# CapacitorBank.net
KiCad netlist of a schematic drawn in Altium Designer
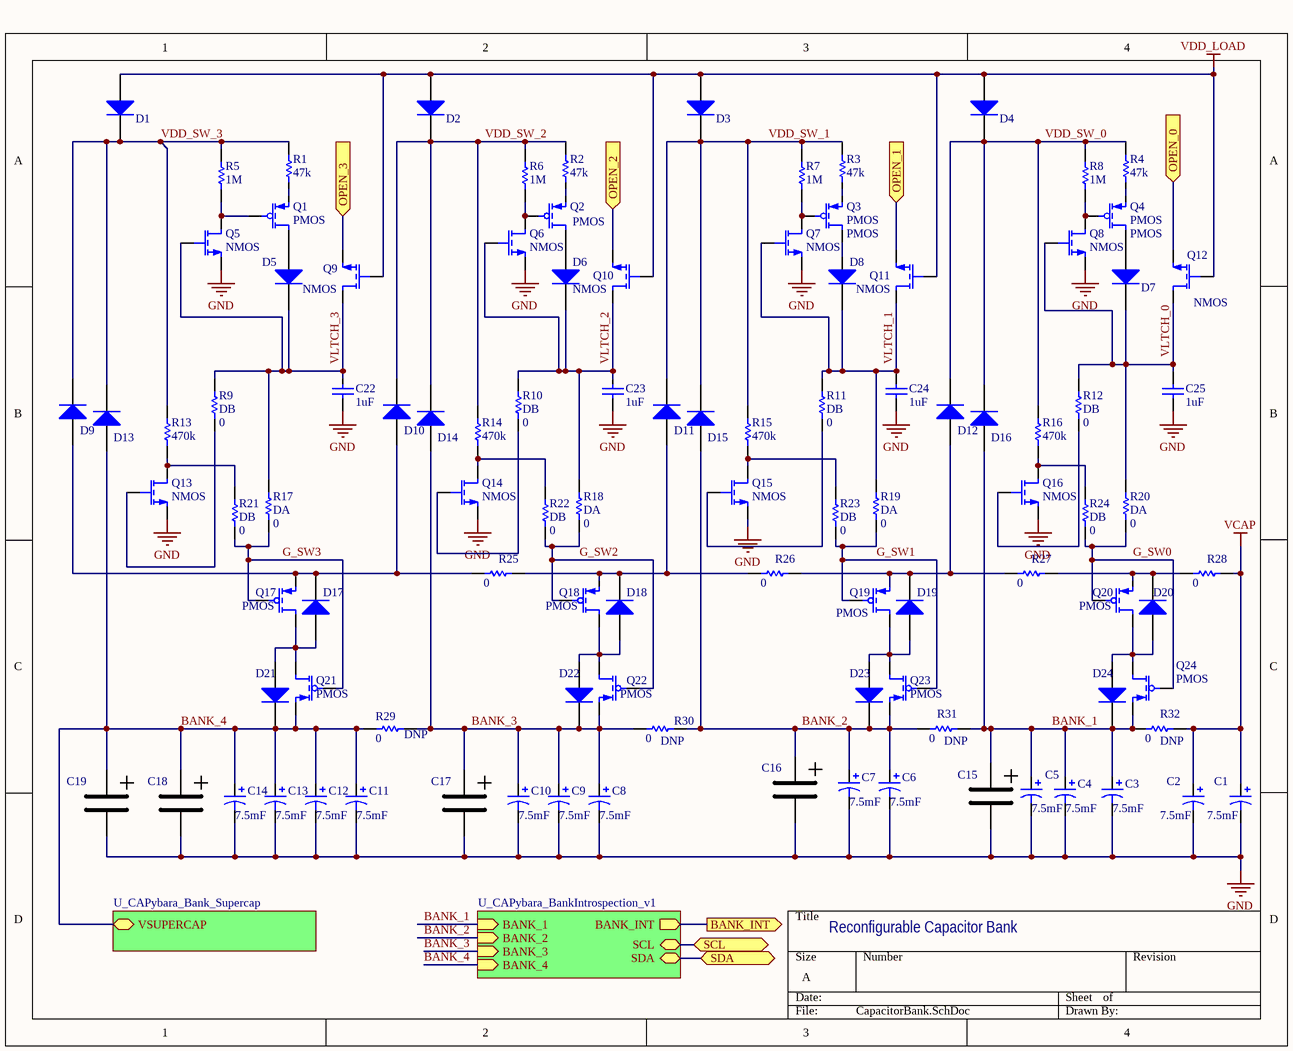
[diagram p0: CapacitorBank.SchDoc]

(export (version "E")
  (design (tool "Eeschema 10.0.6"))
  (components
    (comp (ref "C1")
      (value "7.5mF")
      (footprint "CAP_CPH3225A")
      (description "Polarized Capacitor")
      (fields
        (field (name "DIGI-KEY PART NUMBER") "728-1083-1-ND")
        (field (name "MANUFACTURER PART NUMBER") "CPX3225A752D")
      )
      (libsource (lib "DRP_Basic_2014") (part "Cap - Polarized"))
    )
    (comp (ref "C2")
      (value "7.5mF")
      (footprint "CAP_CPH3225A")
      (description "Polarized Capacitor")
      (fields
        (field (name "DIGI-KEY PART NUMBER") "728-1083-1-ND")
        (field (name "MANUFACTURER PART NUMBER") "CPX3225A752D")
      )
      (libsource (lib "DRP_Basic_2014") (part "Cap - Polarized"))
    )
    (comp (ref "C3")
      (value "7.5mF")
      (footprint "CAP_CPH3225A")
      (description "Polarized Capacitor")
      (fields
        (field (name "DIGI-KEY PART NUMBER") "728-1083-1-ND")
        (field (name "MANUFACTURER PART NUMBER") "CPX3225A752D")
      )
      (libsource (lib "DRP_Basic_2014") (part "Cap - Polarized"))
    )
    (comp (ref "C4")
      (value "7.5mF")
      (footprint "CAP_CPH3225A")
      (description "Polarized Capacitor")
      (fields
        (field (name "DIGI-KEY PART NUMBER") "728-1083-1-ND")
        (field (name "MANUFACTURER PART NUMBER") "CPX3225A752D")
      )
      (libsource (lib "DRP_Basic_2014") (part "Cap - Polarized"))
    )
    (comp (ref "C5")
      (value "7.5mF")
      (footprint "CAP_CPH3225A")
      (description "Polarized Capacitor")
      (fields
        (field (name "DIGI-KEY PART NUMBER") "728-1083-1-ND")
        (field (name "MANUFACTURER PART NUMBER") "CPX3225A752D")
      )
      (libsource (lib "DRP_Basic_2014") (part "Cap - Polarized"))
    )
    (comp (ref "C6")
      (value "7.5mF")
      (footprint "CAP_CPH3225A")
      (description "Polarized Capacitor")
      (fields
        (field (name "DIGI-KEY PART NUMBER") "728-1083-1-ND")
        (field (name "MANUFACTURER PART NUMBER") "CPX3225A752D")
      )
      (libsource (lib "DRP_Basic_2014") (part "Cap - Polarized"))
    )
    (comp (ref "C7")
      (value "7.5mF")
      (footprint "CAP_CPH3225A")
      (description "Polarized Capacitor")
      (fields
        (field (name "DIGI-KEY PART NUMBER") "728-1083-1-ND")
        (field (name "MANUFACTURER PART NUMBER") "CPX3225A752D")
      )
      (libsource (lib "DRP_Basic_2014") (part "Cap - Polarized"))
    )
    (comp (ref "C8")
      (value "7.5mF")
      (footprint "CAP_CPH3225A")
      (description "Polarized Capacitor")
      (fields
        (field (name "DIGI-KEY PART NUMBER") "728-1083-1-ND")
        (field (name "MANUFACTURER PART NUMBER") "CPX3225A752D")
      )
      (libsource (lib "DRP_Basic_2014") (part "Cap - Polarized"))
    )
    (comp (ref "C9")
      (value "7.5mF")
      (footprint "CAP_CPH3225A")
      (description "Polarized Capacitor")
      (fields
        (field (name "DIGI-KEY PART NUMBER") "728-1083-1-ND")
        (field (name "MANUFACTURER PART NUMBER") "CPX3225A752D")
      )
      (libsource (lib "DRP_Basic_2014") (part "Cap - Polarized"))
    )
    (comp (ref "C10")
      (value "7.5mF")
      (footprint "CAP_CPH3225A")
      (description "Polarized Capacitor")
      (fields
        (field (name "DIGI-KEY PART NUMBER") "728-1083-1-ND")
        (field (name "MANUFACTURER PART NUMBER") "CPX3225A752D")
      )
      (libsource (lib "DRP_Basic_2014") (part "Cap - Polarized"))
    )
    (comp (ref "C11")
      (value "7.5mF")
      (footprint "CAP_CPH3225A")
      (description "Polarized Capacitor")
      (fields
        (field (name "DIGI-KEY PART NUMBER") "728-1083-1-ND")
        (field (name "MANUFACTURER PART NUMBER") "CPX3225A752D")
      )
      (libsource (lib "DRP_Basic_2014") (part "Cap - Polarized"))
    )
    (comp (ref "C12")
      (value "7.5mF")
      (footprint "CAP_CPH3225A")
      (description "Polarized Capacitor")
      (fields
        (field (name "DIGI-KEY PART NUMBER") "728-1083-1-ND")
        (field (name "MANUFACTURER PART NUMBER") "CPX3225A752D")
      )
      (libsource (lib "DRP_Basic_2014") (part "Cap - Polarized"))
    )
    (comp (ref "C13")
      (value "7.5mF")
      (footprint "CAP_CPH3225A")
      (description "Polarized Capacitor")
      (fields
        (field (name "DIGI-KEY PART NUMBER") "728-1083-1-ND")
        (field (name "MANUFACTURER PART NUMBER") "CPX3225A752D")
      )
      (libsource (lib "DRP_Basic_2014") (part "Cap - Polarized"))
    )
    (comp (ref "C14")
      (value "7.5mF")
      (footprint "CAP_CPH3225A")
      (description "Polarized Capacitor")
      (fields
        (field (name "DIGI-KEY PART NUMBER") "728-1083-1-ND")
        (field (name "MANUFACTURER PART NUMBER") "CPX3225A752D")
      )
      (libsource (lib "DRP_Basic_2014") (part "Cap - Polarized"))
    )
    (comp (ref "C15")
      (value "304DCN2R7SCBB")
      (footprint "CAP_ILLINOIS_DCN")
      (description "EDLC Supercap")
      (fields
        (field (name "DISTRIBUTOR PART NUMBER") "598-304DCN2R7SCBB")
        (field (name "MANUFACTURER") "Illinois Capacitor / CDE")
      )
      (libsource (lib "Sprite") (part "SUPERCAP"))
    )
    (comp (ref "C16")
      (value "304DCN2R7SCBB")
      (footprint "CAP_ILLINOIS_DCN")
      (description "EDLC Supercap")
      (fields
        (field (name "DISTRIBUTOR PART NUMBER") "598-304DCN2R7SCBB")
        (field (name "MANUFACTURER") "Illinois Capacitor / CDE")
      )
      (libsource (lib "Sprite") (part "SUPERCAP"))
    )
    (comp (ref "C17")
      (value "304DCN2R7SCBB")
      (footprint "CAP_ILLINOIS_DCN")
      (description "EDLC Supercap")
      (fields
        (field (name "DISTRIBUTOR PART NUMBER") "598-304DCN2R7SCBB")
        (field (name "MANUFACTURER") "Illinois Capacitor / CDE")
      )
      (libsource (lib "Sprite") (part "SUPERCAP"))
    )
    (comp (ref "C18")
      (value "304DCN2R7SCBB")
      (footprint "CAP_ILLINOIS_DCN")
      (description "EDLC Supercap")
      (fields
        (field (name "DISTRIBUTOR PART NUMBER") "598-304DCN2R7SCBB")
        (field (name "MANUFACTURER") "Illinois Capacitor / CDE")
      )
      (libsource (lib "Sprite") (part "SUPERCAP"))
    )
    (comp (ref "C19")
      (value "304DCN2R7SCBB")
      (footprint "CAP_ILLINOIS_DCN")
      (description "EDLC Supercap")
      (fields
        (field (name "DISTRIBUTOR PART NUMBER") "598-304DCN2R7SCBB")
        (field (name "MANUFACTURER") "Illinois Capacitor / CDE")
      )
      (libsource (lib "Sprite") (part "SUPERCAP"))
    )
    (comp (ref "C22")
      (value "1uF")
      (footprint "0603")
      (description "Ceramic Capacitor (Surface Mount)")
      (fields
        (field (name "MANUFACTURER") "Murata Electronics North America")
        (field (name "MANUFACTURER PART NUMBER") "GRM188R61A105KA61D")
      )
      (libsource (lib "DRP_Basic_2014") (part "Cap"))
    )
    (comp (ref "C23")
      (value "1uF")
      (footprint "0603")
      (description "Ceramic Capacitor (Surface Mount)")
      (fields
        (field (name "MANUFACTURER") "Murata Electronics North America")
        (field (name "MANUFACTURER PART NUMBER") "GRM188R61A105KA61D")
      )
      (libsource (lib "DRP_Basic_2014") (part "Cap"))
    )
    (comp (ref "C24")
      (value "1uF")
      (footprint "0603")
      (description "Ceramic Capacitor (Surface Mount)")
      (fields
        (field (name "MANUFACTURER") "Murata Electronics North America")
        (field (name "MANUFACTURER PART NUMBER") "GRM188R61A105KA61D")
      )
      (libsource (lib "DRP_Basic_2014") (part "Cap"))
    )
    (comp (ref "C25")
      (value "1uF")
      (footprint "0603")
      (description "Ceramic Capacitor (Surface Mount)")
      (fields
        (field (name "MANUFACTURER") "Murata Electronics North America")
        (field (name "MANUFACTURER PART NUMBER") "GRM188R61A105KA61D")
      )
      (libsource (lib "DRP_Basic_2014") (part "Cap"))
    )
    (comp (ref "D1")
      (value "Diode")
      (footprint "SOD-523")
      (description "General Purpose Diode")
      (fields
        (field (name "MANUFACTURER") "Vishay Semiconductor")
        (field (name "MANUFACTURER PART NUMBER") "BAS40-02V-V-G-08")
      )
      (libsource (lib "DRP_Basic_2014") (part "Diode"))
    )
    (comp (ref "D2")
      (value "Diode")
      (footprint "SOD-523")
      (description "General Purpose Diode")
      (fields
        (field (name "MANUFACTURER") "Vishay Semiconductor")
        (field (name "MANUFACTURER PART NUMBER") "BAS40-02V-V-G-08")
      )
      (libsource (lib "DRP_Basic_2014") (part "Diode"))
    )
    (comp (ref "D3")
      (value "Diode")
      (footprint "SOD-523")
      (description "General Purpose Diode")
      (fields
        (field (name "MANUFACTURER") "Vishay Semiconductor")
        (field (name "MANUFACTURER PART NUMBER") "BAS40-02V-V-G-08")
      )
      (libsource (lib "DRP_Basic_2014") (part "Diode"))
    )
    (comp (ref "D4")
      (value "Diode")
      (footprint "SOD-523")
      (description "General Purpose Diode")
      (fields
        (field (name "MANUFACTURER") "Vishay Semiconductor")
        (field (name "MANUFACTURER PART NUMBER") "BAS40-02V-V-G-08")
      )
      (libsource (lib "DRP_Basic_2014") (part "Diode"))
    )
    (comp (ref "D5")
      (value "Diode")
      (footprint "SOD-523")
      (description "General Purpose Diode")
      (fields
        (field (name "MANUFACTURER") "Vishay Semiconductor")
        (field (name "MANUFACTURER PART NUMBER") "BAS40-02V-V-G-08")
      )
      (libsource (lib "DRP_Basic_2014") (part "Diode"))
    )
    (comp (ref "D6")
      (value "Diode")
      (footprint "SOD-523")
      (description "General Purpose Diode")
      (fields
        (field (name "MANUFACTURER") "Vishay Semiconductor")
        (field (name "MANUFACTURER PART NUMBER") "BAS40-02V-V-G-08")
      )
      (libsource (lib "DRP_Basic_2014") (part "Diode"))
    )
    (comp (ref "D7")
      (value "Diode")
      (footprint "SOD-523")
      (description "General Purpose Diode")
      (fields
        (field (name "MANUFACTURER") "Vishay Semiconductor")
        (field (name "MANUFACTURER PART NUMBER") "BAS40-02V-V-G-08")
      )
      (libsource (lib "DRP_Basic_2014") (part "Diode"))
    )
    (comp (ref "D8")
      (value "Diode")
      (footprint "SOD-523")
      (description "General Purpose Diode")
      (fields
        (field (name "MANUFACTURER") "Vishay Semiconductor")
        (field (name "MANUFACTURER PART NUMBER") "BAS40-02V-V-G-08")
      )
      (libsource (lib "") (part "Diode_1"))
    )
    (comp (ref "D9")
      (value "Diode")
      (footprint "SOD-523")
      (description "General Purpose Diode")
      (fields
        (field (name "MANUFACTURER") "Vishay Semiconductor")
        (field (name "MANUFACTURER PART NUMBER") "BAS40-02V-V-G-08")
      )
      (libsource (lib "DRP_Basic_2014") (part "Diode"))
    )
    (comp (ref "D10")
      (value "Diode")
      (footprint "SOD-523")
      (description "General Purpose Diode")
      (fields
        (field (name "MANUFACTURER") "Vishay Semiconductor")
        (field (name "MANUFACTURER PART NUMBER") "BAS40-02V-V-G-08")
      )
      (libsource (lib "DRP_Basic_2014") (part "Diode"))
    )
    (comp (ref "D11")
      (value "Diode")
      (footprint "SOD-523")
      (description "General Purpose Diode")
      (fields
        (field (name "MANUFACTURER") "Vishay Semiconductor")
        (field (name "MANUFACTURER PART NUMBER") "BAS40-02V-V-G-08")
      )
      (libsource (lib "DRP_Basic_2014") (part "Diode"))
    )
    (comp (ref "D12")
      (value "Diode")
      (footprint "SOD-523")
      (description "General Purpose Diode")
      (fields
        (field (name "MANUFACTURER") "Vishay Semiconductor")
        (field (name "MANUFACTURER PART NUMBER") "BAS40-02V-V-G-08")
      )
      (libsource (lib "DRP_Basic_2014") (part "Diode"))
    )
    (comp (ref "D13")
      (value "Diode")
      (footprint "SOD-523")
      (description "General Purpose Diode")
      (fields
        (field (name "MANUFACTURER") "Vishay Semiconductor")
        (field (name "MANUFACTURER PART NUMBER") "BAS40-02V-V-G-08")
      )
      (libsource (lib "DRP_Basic_2014") (part "Diode"))
    )
    (comp (ref "D14")
      (value "Diode")
      (footprint "SOD-523")
      (description "General Purpose Diode")
      (fields
        (field (name "MANUFACTURER") "Vishay Semiconductor")
        (field (name "MANUFACTURER PART NUMBER") "BAS40-02V-V-G-08")
      )
      (libsource (lib "DRP_Basic_2014") (part "Diode"))
    )
    (comp (ref "D15")
      (value "Diode")
      (footprint "SOD-523")
      (description "General Purpose Diode")
      (fields
        (field (name "MANUFACTURER") "Vishay Semiconductor")
        (field (name "MANUFACTURER PART NUMBER") "BAS40-02V-V-G-08")
      )
      (libsource (lib "DRP_Basic_2014") (part "Diode"))
    )
    (comp (ref "D16")
      (value "Diode")
      (footprint "SOD-523")
      (description "General Purpose Diode")
      (fields
        (field (name "MANUFACTURER") "Vishay Semiconductor")
        (field (name "MANUFACTURER PART NUMBER") "BAS40-02V-V-G-08")
      )
      (libsource (lib "DRP_Basic_2014") (part "Diode"))
    )
    (comp (ref "D17")
      (value "Diode")
      (footprint "SOD-523")
      (description "General Purpose Diode")
      (fields
        (field (name "MANUFACTURER") "Vishay Semiconductor")
        (field (name "MANUFACTURER PART NUMBER") "BAS40-02V-V-G-08")
      )
      (libsource (lib "DRP_Basic_2014") (part "Diode"))
    )
    (comp (ref "D18")
      (value "Diode")
      (footprint "SOD-523")
      (description "General Purpose Diode")
      (fields
        (field (name "MANUFACTURER") "Vishay Semiconductor")
        (field (name "MANUFACTURER PART NUMBER") "BAS40-02V-V-G-08")
      )
      (libsource (lib "DRP_Basic_2014") (part "Diode"))
    )
    (comp (ref "D19")
      (value "Diode")
      (footprint "SOD-523")
      (description "General Purpose Diode")
      (fields
        (field (name "MANUFACTURER") "Vishay Semiconductor")
        (field (name "MANUFACTURER PART NUMBER") "BAS40-02V-V-G-08")
      )
      (libsource (lib "DRP_Basic_2014") (part "Diode"))
    )
    (comp (ref "D20")
      (value "Diode")
      (footprint "SOD-523")
      (description "General Purpose Diode")
      (fields
        (field (name "MANUFACTURER") "Vishay Semiconductor")
        (field (name "MANUFACTURER PART NUMBER") "BAS40-02V-V-G-08")
      )
      (libsource (lib "DRP_Basic_2014") (part "Diode"))
    )
    (comp (ref "D21")
      (value "Diode")
      (footprint "SOD-523")
      (description "General Purpose Diode")
      (fields
        (field (name "MANUFACTURER") "Vishay Semiconductor")
        (field (name "MANUFACTURER PART NUMBER") "BAS40-02V-V-G-08")
      )
      (libsource (lib "DRP_Basic_2014") (part "Diode"))
    )
    (comp (ref "D22")
      (value "Diode")
      (footprint "SOD-523")
      (description "General Purpose Diode")
      (fields
        (field (name "MANUFACTURER") "Vishay Semiconductor")
        (field (name "MANUFACTURER PART NUMBER") "BAS40-02V-V-G-08")
      )
      (libsource (lib "DRP_Basic_2014") (part "Diode"))
    )
    (comp (ref "D23")
      (value "Diode")
      (footprint "SOD-523")
      (description "General Purpose Diode")
      (fields
        (field (name "MANUFACTURER") "Vishay Semiconductor")
        (field (name "MANUFACTURER PART NUMBER") "BAS40-02V-V-G-08")
      )
      (libsource (lib "DRP_Basic_2014") (part "Diode"))
    )
    (comp (ref "D24")
      (value "Diode")
      (footprint "SOD-523")
      (description "General Purpose Diode")
      (fields
        (field (name "MANUFACTURER") "Vishay Semiconductor")
        (field (name "MANUFACTURER PART NUMBER") "BAS40-02V-V-G-08")
      )
      (libsource (lib "DRP_Basic_2014") (part "Diode"))
    )
    (comp (ref "Q1")
      (value "PMOS")
      (footprint "SOT23 - N")
      (description "P-Channel MOSFET")
      (fields
        (field (name "DIGI-KEY PART NUMBER") "1727-2531-1-ND")
        (field (name "MANUFACTURER PART NUMBER") "PMV30XPEAR")
      )
      (libsource (lib "DRP_Basic_2014") (part "MOSFET-P"))
    )
    (comp (ref "Q2")
      (value "PMOS")
      (footprint "SOT23 - N")
      (description "P-Channel MOSFET")
      (fields
        (field (name "DIGI-KEY PART NUMBER") "1727-2531-1-ND")
        (field (name "MANUFACTURER PART NUMBER") "PMV30XPEAR")
      )
      (libsource (lib "DRP_Basic_2014") (part "MOSFET-P"))
    )
    (comp (ref "Q3")
      (value "PMOS")
      (footprint "SOT23 - N")
      (description "P-Channel MOSFET")
      (fields
        (field (name "DIGI-KEY PART NUMBER") "1727-2531-1-ND")
        (field (name "MANUFACTURER PART NUMBER") "PMV30XPEAR")
        (field (name "ALTIUM_VALUE") "PMOS")
      )
      (libsource (lib "DRP_Basic_2014") (part "MOSFET-P"))
    )
    (comp (ref "Q4")
      (value "PMOS")
      (footprint "SOT23 - N")
      (description "P-Channel MOSFET")
      (fields
        (field (name "DIGI-KEY PART NUMBER") "1727-2531-1-ND")
        (field (name "MANUFACTURER PART NUMBER") "PMV30XPEAR")
        (field (name "ALTIUM_VALUE") "PMOS")
      )
      (libsource (lib "DRP_Basic_2014") (part "MOSFET-P"))
    )
    (comp (ref "Q5")
      (value "NMOS")
      (footprint "SOT23 - N")
      (description "N-Channel MOSFET")
      (fields
        (field (name "DIGI-KEY PART NUMBER") "SI2302CDS-T1-E3CT-ND")
        (field (name "MANUFACTURER PART NUMBER") "SI2302CDS-T1-E3")
      )
      (libsource (lib "DRP_Basic_2014") (part "MOSFET-N"))
    )
    (comp (ref "Q6")
      (value "NMOS")
      (footprint "SOT23 - N")
      (description "N-Channel MOSFET")
      (fields
        (field (name "DIGI-KEY PART NUMBER") "SI2302CDS-T1-E3CT-ND")
        (field (name "MANUFACTURER PART NUMBER") "SI2302CDS-T1-E3")
      )
      (libsource (lib "DRP_Basic_2014") (part "MOSFET-N"))
    )
    (comp (ref "Q7")
      (value "NMOS")
      (footprint "SOT23 - N")
      (description "N-Channel MOSFET")
      (fields
        (field (name "DIGI-KEY PART NUMBER") "SI2302CDS-T1-E3CT-ND")
        (field (name "MANUFACTURER PART NUMBER") "SI2302CDS-T1-E3")
      )
      (libsource (lib "DRP_Basic_2014") (part "MOSFET-N"))
    )
    (comp (ref "Q8")
      (value "NMOS")
      (footprint "SOT23 - N")
      (description "N-Channel MOSFET")
      (fields
        (field (name "DIGI-KEY PART NUMBER") "SI2302CDS-T1-E3CT-ND")
        (field (name "MANUFACTURER PART NUMBER") "SI2302CDS-T1-E3")
      )
      (libsource (lib "DRP_Basic_2014") (part "MOSFET-N"))
    )
    (comp (ref "Q9")
      (value "NMOS")
      (footprint "SOT23 - N")
      (description "N-Channel MOSFET")
      (fields
        (field (name "DIGI-KEY PART NUMBER") "DMN65D8L-7DICT-ND")
        (field (name "MANUFACTURER PART NUMBER") "DMN65D8L-7")
      )
      (libsource (lib "DRP_Basic_2014") (part "MOSFET-N"))
    )
    (comp (ref "Q10")
      (value "NMOS")
      (footprint "SOT23 - N")
      (description "N-Channel MOSFET")
      (fields
        (field (name "DIGI-KEY PART NUMBER") "DMN65D8L-7DICT-ND")
        (field (name "MANUFACTURER PART NUMBER") "DMN65D8L-7")
      )
      (libsource (lib "DRP_Basic_2014") (part "MOSFET-N"))
    )
    (comp (ref "Q11")
      (value "NMOS")
      (footprint "SOT23 - N")
      (description "N-Channel MOSFET")
      (fields
        (field (name "DIGI-KEY PART NUMBER") "DMN65D8L-7DICT-ND")
        (field (name "MANUFACTURER PART NUMBER") "DMN65D8L-7")
      )
      (libsource (lib "DRP_Basic_2014") (part "MOSFET-N"))
    )
    (comp (ref "Q12")
      (value "NMOS")
      (footprint "SOT23 - N")
      (description "N-Channel MOSFET")
      (fields
        (field (name "DIGI-KEY PART NUMBER") "DMN65D8L-7DICT-ND")
        (field (name "MANUFACTURER PART NUMBER") "DMN65D8L-7")
      )
      (libsource (lib "DRP_Basic_2014") (part "MOSFET-N"))
    )
    (comp (ref "Q13")
      (value "NMOS")
      (footprint "SOT23 - N")
      (description "N-Channel MOSFET")
      (fields
        (field (name "DIGI-KEY PART NUMBER") "SI2302CDS-T1-E3CT-ND")
        (field (name "MANUFACTURER PART NUMBER") "SI2302CDS-T1-E3")
      )
      (libsource (lib "DRP_Basic_2014") (part "MOSFET-N"))
    )
    (comp (ref "Q14")
      (value "NMOS")
      (footprint "SOT23 - N")
      (description "N-Channel MOSFET")
      (fields
        (field (name "DIGI-KEY PART NUMBER") "SI2302CDS-T1-E3CT-ND")
        (field (name "MANUFACTURER PART NUMBER") "SI2302CDS-T1-E3")
      )
      (libsource (lib "DRP_Basic_2014") (part "MOSFET-N"))
    )
    (comp (ref "Q15")
      (value "NMOS")
      (footprint "SOT23 - N")
      (description "N-Channel MOSFET")
      (fields
        (field (name "DIGI-KEY PART NUMBER") "SI2302CDS-T1-E3CT-ND")
        (field (name "MANUFACTURER PART NUMBER") "SI2302CDS-T1-E3")
      )
      (libsource (lib "DRP_Basic_2014") (part "MOSFET-N"))
    )
    (comp (ref "Q16")
      (value "NMOS")
      (footprint "SOT23 - N")
      (description "N-Channel MOSFET")
      (fields
        (field (name "DIGI-KEY PART NUMBER") "SI2302CDS-T1-E3CT-ND")
        (field (name "MANUFACTURER PART NUMBER") "SI2302CDS-T1-E3")
      )
      (libsource (lib "DRP_Basic_2014") (part "MOSFET-N"))
    )
    (comp (ref "Q17")
      (value "PMOS")
      (footprint "SOT23 - N")
      (description "P-Channel MOSFET")
      (fields
        (field (name "DIGI-KEY PART NUMBER") "1727-2531-1-ND")
        (field (name "MANUFACTURER PART NUMBER") "PMV30XPEAR")
      )
      (libsource (lib "DRP_Basic_2014") (part "MOSFET-P"))
    )
    (comp (ref "Q18")
      (value "PMOS")
      (footprint "SOT23 - N")
      (description "P-Channel MOSFET")
      (fields
        (field (name "DIGI-KEY PART NUMBER") "1727-2531-1-ND")
        (field (name "MANUFACTURER PART NUMBER") "PMV30XPEAR")
      )
      (libsource (lib "DRP_Basic_2014") (part "MOSFET-P"))
    )
    (comp (ref "Q19")
      (value "PMOS")
      (footprint "SOT23 - N")
      (description "P-Channel MOSFET")
      (fields
        (field (name "DIGI-KEY PART NUMBER") "1727-2531-1-ND")
        (field (name "MANUFACTURER PART NUMBER") "PMV30XPEAR")
      )
      (libsource (lib "DRP_Basic_2014") (part "MOSFET-P"))
    )
    (comp (ref "Q20")
      (value "PMOS")
      (footprint "SOT23 - N")
      (description "P-Channel MOSFET")
      (fields
        (field (name "DIGI-KEY PART NUMBER") "1727-2531-1-ND")
        (field (name "MANUFACTURER PART NUMBER") "PMV30XPEAR")
      )
      (libsource (lib "DRP_Basic_2014") (part "MOSFET-P"))
    )
    (comp (ref "Q21")
      (value "PMOS")
      (footprint "SOT23 - N")
      (description "P-Channel MOSFET")
      (fields
        (field (name "DIGI-KEY PART NUMBER") "1727-2531-1-ND")
        (field (name "MANUFACTURER PART NUMBER") "PMV30XPEAR")
      )
      (libsource (lib "DRP_Basic_2014") (part "MOSFET-P"))
    )
    (comp (ref "Q22")
      (value "PMOS")
      (footprint "SOT23 - N")
      (description "P-Channel MOSFET")
      (fields
        (field (name "DIGI-KEY PART NUMBER") "1727-2531-1-ND")
        (field (name "MANUFACTURER PART NUMBER") "PMV30XPEAR")
      )
      (libsource (lib "DRP_Basic_2014") (part "MOSFET-P"))
    )
    (comp (ref "Q23")
      (value "PMOS")
      (footprint "SOT23 - N")
      (description "P-Channel MOSFET")
      (fields
        (field (name "DIGI-KEY PART NUMBER") "1727-2531-1-ND")
        (field (name "MANUFACTURER PART NUMBER") "PMV30XPEAR")
      )
      (libsource (lib "DRP_Basic_2014") (part "MOSFET-P"))
    )
    (comp (ref "Q24")
      (value "PMOS")
      (footprint "SOT23 - N")
      (description "P-Channel MOSFET")
      (fields
        (field (name "DIGI-KEY PART NUMBER") "1727-2531-1-ND")
        (field (name "MANUFACTURER PART NUMBER") "PMV30XPEAR")
      )
      (libsource (lib "DRP_Basic_2014") (part "MOSFET-P"))
    )
    (comp (ref "R1")
      (value "47k")
      (footprint "0603")
      (description "Chip Resistor (Surface Mount)")
      (fields
        (field (name "MANUFACTURER") "Yageo")
        (field (name "MANUFACTURER PART NUMBER") "RT0603DRD0747KL")
      )
      (libsource (lib "DRP_Basic_2014") (part "Res"))
    )
    (comp (ref "R2")
      (value "47k")
      (footprint "0603")
      (description "Chip Resistor (Surface Mount)")
      (fields
        (field (name "MANUFACTURER") "Yageo")
        (field (name "MANUFACTURER PART NUMBER") "RT0603DRD0747KL")
      )
      (libsource (lib "DRP_Basic_2014") (part "Res"))
    )
    (comp (ref "R3")
      (value "47k")
      (footprint "0603")
      (description "Chip Resistor (Surface Mount)")
      (fields
        (field (name "MANUFACTURER") "Yageo")
        (field (name "MANUFACTURER PART NUMBER") "RT0603DRD0747KL")
      )
      (libsource (lib "DRP_Basic_2014") (part "Res"))
    )
    (comp (ref "R4")
      (value "47k")
      (footprint "0603")
      (description "Chip Resistor (Surface Mount)")
      (fields
        (field (name "MANUFACTURER") "Yageo")
        (field (name "MANUFACTURER PART NUMBER") "RT0603DRD0747KL")
      )
      (libsource (lib "DRP_Basic_2014") (part "Res"))
    )
    (comp (ref "R5")
      (value "1M")
      (footprint "0603")
      (description "Chip Resistor (Surface Mount)")
      (fields
        (field (name "MANUFACTURER") "Yageo")
        (field (name "MANUFACTURER PART NUMBER") "RC0603FR-071ML")
      )
      (libsource (lib "DRP_Basic_2014") (part "Res"))
    )
    (comp (ref "R6")
      (value "1M")
      (footprint "0603")
      (description "Chip Resistor (Surface Mount)")
      (fields
        (field (name "MANUFACTURER") "Yageo")
        (field (name "MANUFACTURER PART NUMBER") "RC0603FR-071ML")
      )
      (libsource (lib "DRP_Basic_2014") (part "Res"))
    )
    (comp (ref "R7")
      (value "1M")
      (footprint "0603")
      (description "Chip Resistor (Surface Mount)")
      (fields
        (field (name "MANUFACTURER") "Yageo")
        (field (name "MANUFACTURER PART NUMBER") "RC0603FR-071ML")
      )
      (libsource (lib "DRP_Basic_2014") (part "Res"))
    )
    (comp (ref "R8")
      (value "1M")
      (footprint "0603")
      (description "Chip Resistor (Surface Mount)")
      (fields
        (field (name "MANUFACTURER") "Yageo")
        (field (name "MANUFACTURER PART NUMBER") "RC0603FR-071ML")
      )
      (libsource (lib "DRP_Basic_2014") (part "Res"))
    )
    (comp (ref "R9")
      (value "DB")
      (footprint "0603")
      (description "Chip Resistor (Surface Mount)")
      (fields
        (field (name "MANUFACTURER") "Yageo")
        (field (name "MANUFACTURER PART NUMBER") "RC0603JR-070RL")
        (field (name "ALTIUM_VALUE") "0")
      )
      (libsource (lib "DRP_Basic_2014") (part "Res"))
    )
    (comp (ref "R10")
      (value "DB")
      (footprint "0603")
      (description "Chip Resistor (Surface Mount)")
      (fields
        (field (name "MANUFACTURER") "Yageo")
        (field (name "MANUFACTURER PART NUMBER") "RC0603JR-070RL")
        (field (name "ALTIUM_VALUE") "0")
      )
      (libsource (lib "DRP_Basic_2014") (part "Res"))
    )
    (comp (ref "R11")
      (value "DB")
      (footprint "0603")
      (description "Chip Resistor (Surface Mount)")
      (fields
        (field (name "MANUFACTURER") "Yageo")
        (field (name "MANUFACTURER PART NUMBER") "RC0603JR-070RL")
        (field (name "ALTIUM_VALUE") "0")
      )
      (libsource (lib "DRP_Basic_2014") (part "Res"))
    )
    (comp (ref "R12")
      (value "DB")
      (footprint "0603")
      (description "Chip Resistor (Surface Mount)")
      (fields
        (field (name "MANUFACTURER") "Yageo")
        (field (name "MANUFACTURER PART NUMBER") "RC0603JR-070RL")
        (field (name "ALTIUM_VALUE") "0")
      )
      (libsource (lib "DRP_Basic_2014") (part "Res"))
    )
    (comp (ref "R13")
      (value "470k")
      (footprint "0603")
      (description "Chip Resistor (Surface Mount)")
      (fields
        (field (name "MANUFACTURER") "Yageo")
        (field (name "MANUFACTURER PART NUMBER") "RC0603FR-07470KL")
      )
      (libsource (lib "DRP_Basic_2014") (part "Res"))
    )
    (comp (ref "R14")
      (value "470k")
      (footprint "0603")
      (description "Chip Resistor (Surface Mount)")
      (fields
        (field (name "MANUFACTURER") "Yageo")
        (field (name "MANUFACTURER PART NUMBER") "RC0603FR-07470KL")
      )
      (libsource (lib "DRP_Basic_2014") (part "Res"))
    )
    (comp (ref "R15")
      (value "470k")
      (footprint "0603")
      (description "Chip Resistor (Surface Mount)")
      (fields
        (field (name "MANUFACTURER") "Yageo")
        (field (name "MANUFACTURER PART NUMBER") "RC0603FR-07470KL")
      )
      (libsource (lib "DRP_Basic_2014") (part "Res"))
    )
    (comp (ref "R16")
      (value "470k")
      (footprint "0603")
      (description "Chip Resistor (Surface Mount)")
      (fields
        (field (name "MANUFACTURER") "Yageo")
        (field (name "MANUFACTURER PART NUMBER") "RC0603FR-07470KL")
      )
      (libsource (lib "DRP_Basic_2014") (part "Res"))
    )
    (comp (ref "R17")
      (value "DA")
      (footprint "0603")
      (description "Chip Resistor (Surface Mount)")
      (fields
        (field (name "MANUFACTURER") "Yageo")
        (field (name "MANUFACTURER PART NUMBER") "RC0603JR-070RL")
        (field (name "ALTIUM_VALUE") "0")
      )
      (libsource (lib "DRP_Basic_2014") (part "Res"))
    )
    (comp (ref "R18")
      (value "DA")
      (footprint "0603")
      (description "Chip Resistor (Surface Mount)")
      (fields
        (field (name "MANUFACTURER") "Yageo")
        (field (name "MANUFACTURER PART NUMBER") "RC0603JR-070RL")
        (field (name "ALTIUM_VALUE") "0")
      )
      (libsource (lib "DRP_Basic_2014") (part "Res"))
    )
    (comp (ref "R19")
      (value "DA")
      (footprint "0603")
      (description "Chip Resistor (Surface Mount)")
      (fields
        (field (name "MANUFACTURER") "Yageo")
        (field (name "MANUFACTURER PART NUMBER") "RC0603JR-070RL")
        (field (name "ALTIUM_VALUE") "0")
      )
      (libsource (lib "DRP_Basic_2014") (part "Res"))
    )
    (comp (ref "R20")
      (value "DA")
      (footprint "0603")
      (description "Chip Resistor (Surface Mount)")
      (fields
        (field (name "MANUFACTURER") "Yageo")
        (field (name "MANUFACTURER PART NUMBER") "RC0603JR-070RL")
        (field (name "ALTIUM_VALUE") "0")
      )
      (libsource (lib "DRP_Basic_2014") (part "Res"))
    )
    (comp (ref "R21")
      (value "DB")
      (footprint "0603")
      (description "Chip Resistor (Surface Mount)")
      (fields
        (field (name "MANUFACTURER") "Yageo")
        (field (name "MANUFACTURER PART NUMBER") "RC0603JR-070RL")
        (field (name "ALTIUM_VALUE") "0")
      )
      (libsource (lib "DRP_Basic_2014") (part "Res"))
    )
    (comp (ref "R22")
      (value "DB")
      (footprint "0603")
      (description "Chip Resistor (Surface Mount)")
      (fields
        (field (name "MANUFACTURER") "Yageo")
        (field (name "MANUFACTURER PART NUMBER") "RC0603JR-070RL")
        (field (name "ALTIUM_VALUE") "0")
      )
      (libsource (lib "DRP_Basic_2014") (part "Res"))
    )
    (comp (ref "R23")
      (value "DB")
      (footprint "0603")
      (description "Chip Resistor (Surface Mount)")
      (fields
        (field (name "MANUFACTURER") "Yageo")
        (field (name "MANUFACTURER PART NUMBER") "RC0603JR-070RL")
        (field (name "ALTIUM_VALUE") "0")
      )
      (libsource (lib "DRP_Basic_2014") (part "Res"))
    )
    (comp (ref "R24")
      (value "DB")
      (footprint "0603")
      (description "Chip Resistor (Surface Mount)")
      (fields
        (field (name "MANUFACTURER") "Yageo")
        (field (name "MANUFACTURER PART NUMBER") "RC0603JR-070RL")
        (field (name "ALTIUM_VALUE") "0")
      )
      (libsource (lib "DRP_Basic_2014") (part "Res"))
    )
    (comp (ref "R25")
      (value "0")
      (footprint "0603")
      (description "Chip Resistor (Surface Mount)")
      (fields
        (field (name "MANUFACTURER") "Yageo")
        (field (name "MANUFACTURER PART NUMBER") "RC0603JR-070RL")
      )
      (libsource (lib "DRP_Basic_2014") (part "Res"))
    )
    (comp (ref "R26")
      (value "0")
      (footprint "0603")
      (description "Chip Resistor (Surface Mount)")
      (fields
        (field (name "MANUFACTURER") "Yageo")
        (field (name "MANUFACTURER PART NUMBER") "RC0603JR-070RL")
      )
      (libsource (lib "DRP_Basic_2014") (part "Res"))
    )
    (comp (ref "R27")
      (value "0")
      (footprint "0603")
      (description "Chip Resistor (Surface Mount)")
      (fields
        (field (name "MANUFACTURER") "Yageo")
        (field (name "MANUFACTURER PART NUMBER") "RC0603JR-070RL")
      )
      (libsource (lib "DRP_Basic_2014") (part "Res"))
    )
    (comp (ref "R28")
      (value "0")
      (footprint "0603")
      (description "Chip Resistor (Surface Mount)")
      (fields
        (field (name "MANUFACTURER") "Yageo")
        (field (name "MANUFACTURER PART NUMBER") "RC0603JR-070RL")
      )
      (libsource (lib "DRP_Basic_2014") (part "Res"))
    )
    (comp (ref "R29")
      (value "0")
      (footprint "0603")
      (description "Chip Resistor (Surface Mount)")
      (fields
        (field (name "MANUFACTURER") "Yageo")
        (field (name "MANUFACTURER PART NUMBER") "RC0603JR-070RL")
        (field (name "NOTE") "DNP")
      )
      (libsource (lib "DRP_Basic_2014") (part "Res"))
    )
    (comp (ref "R30")
      (value "0")
      (footprint "0603")
      (description "Chip Resistor (Surface Mount)")
      (fields
        (field (name "MANUFACTURER") "Yageo")
        (field (name "MANUFACTURER PART NUMBER") "RC0603JR-070RL")
        (field (name "NOTE") "DNP")
      )
      (libsource (lib "DRP_Basic_2014") (part "Res"))
    )
    (comp (ref "R31")
      (value "0")
      (footprint "0603")
      (description "Chip Resistor (Surface Mount)")
      (fields
        (field (name "MANUFACTURER") "Yageo")
        (field (name "MANUFACTURER PART NUMBER") "RC0603JR-070RL")
        (field (name "NOTE") "DNP")
      )
      (libsource (lib "DRP_Basic_2014") (part "Res"))
    )
    (comp (ref "R32")
      (value "0")
      (footprint "0603")
      (description "Chip Resistor (Surface Mount)")
      (fields
        (field (name "MANUFACTURER") "Yageo")
        (field (name "MANUFACTURER PART NUMBER") "RC0603JR-070RL")
        (field (name "NOTE") "DNP")
      )
      (libsource (lib "DRP_Basic_2014") (part "Res"))
    )
  )
  (nets
    (net (code "1") (name "/BANK_1") (class "Default")
      (node (ref "C15") (pin "1") (pinfunction "P_1") (pintype "passive"))
      (node (ref "C3") (pin "1") (pinfunction "1_1") (pintype "passive"))
      (node (ref "C4") (pin "1") (pinfunction "1_1") (pintype "passive"))
      (node (ref "C5") (pin "1") (pinfunction "1_1") (pintype "passive"))
      (node (ref "D16") (pin "1") (pinfunction "A_1") (pintype "passive"))
      (node (ref "D24") (pin "2") (pinfunction "C_2") (pintype "passive"))
      (node (ref "Q24") (pin "2") (pinfunction "S_2") (pintype "passive"))
      (node (ref "R31") (pin "2") (pinfunction "2_2") (pintype "passive"))
      (node (ref "R32") (pin "1") (pinfunction "1_1") (pintype "passive"))
    )
    (net (code "2") (name "/BANK_2") (class "Default")
      (node (ref "C16") (pin "1") (pinfunction "P_1") (pintype "passive"))
      (node (ref "C6") (pin "1") (pinfunction "1_1") (pintype "passive"))
      (node (ref "C7") (pin "1") (pinfunction "1_1") (pintype "passive"))
      (node (ref "D15") (pin "1") (pinfunction "A_1") (pintype "passive"))
      (node (ref "D23") (pin "2") (pinfunction "C_2") (pintype "passive"))
      (node (ref "Q23") (pin "2") (pinfunction "S_2") (pintype "passive"))
      (node (ref "R30") (pin "2") (pinfunction "2_2") (pintype "passive"))
      (node (ref "R31") (pin "1") (pinfunction "1_1") (pintype "passive"))
    )
    (net (code "3") (name "/BANK_3") (class "Default")
      (node (ref "C10") (pin "1") (pinfunction "1_1") (pintype "passive"))
      (node (ref "C17") (pin "1") (pinfunction "P_1") (pintype "passive"))
      (node (ref "C8") (pin "1") (pinfunction "1_1") (pintype "passive"))
      (node (ref "C9") (pin "1") (pinfunction "1_1") (pintype "passive"))
      (node (ref "D14") (pin "1") (pinfunction "A_1") (pintype "passive"))
      (node (ref "D22") (pin "2") (pinfunction "C_2") (pintype "passive"))
      (node (ref "Q22") (pin "2") (pinfunction "S_2") (pintype "passive"))
      (node (ref "R29") (pin "2") (pinfunction "2_2") (pintype "passive"))
      (node (ref "R30") (pin "1") (pinfunction "1_1") (pintype "passive"))
    )
    (net (code "4") (name "/BANK_4") (class "Default")
      (node (ref "C11") (pin "1") (pinfunction "1_1") (pintype "passive"))
      (node (ref "C12") (pin "1") (pinfunction "1_1") (pintype "passive"))
      (node (ref "C13") (pin "1") (pinfunction "1_1") (pintype "passive"))
      (node (ref "C14") (pin "1") (pinfunction "1_1") (pintype "passive"))
      (node (ref "C18") (pin "1") (pinfunction "P_1") (pintype "passive"))
      (node (ref "C19") (pin "1") (pinfunction "P_1") (pintype "passive"))
      (node (ref "D13") (pin "1") (pinfunction "A_1") (pintype "passive"))
      (node (ref "D21") (pin "2") (pinfunction "C_2") (pintype "passive"))
      (node (ref "Q21") (pin "2") (pinfunction "S_2") (pintype "passive"))
      (node (ref "R29") (pin "1") (pinfunction "1_1") (pintype "passive"))
    )
    (net (code "6") (name "/G_SW0") (class "Default")
      (node (ref "Q20") (pin "1") (pinfunction "G_1") (pintype "passive"))
      (node (ref "Q24") (pin "1") (pinfunction "G_1") (pintype "passive"))
      (node (ref "R20") (pin "1") (pinfunction "1_1") (pintype "passive"))
      (node (ref "R24") (pin "1") (pinfunction "1_1") (pintype "passive"))
    )
    (net (code "7") (name "/G_SW1") (class "Default")
      (node (ref "Q19") (pin "1") (pinfunction "G_1") (pintype "passive"))
      (node (ref "Q23") (pin "1") (pinfunction "G_1") (pintype "passive"))
      (node (ref "R19") (pin "1") (pinfunction "1_1") (pintype "passive"))
      (node (ref "R23") (pin "1") (pinfunction "1_1") (pintype "passive"))
    )
    (net (code "8") (name "/G_SW2") (class "Default")
      (node (ref "Q18") (pin "1") (pinfunction "G_1") (pintype "passive"))
      (node (ref "Q22") (pin "1") (pinfunction "G_1") (pintype "passive"))
      (node (ref "R18") (pin "1") (pinfunction "1_1") (pintype "passive"))
      (node (ref "R22") (pin "1") (pinfunction "1_1") (pintype "passive"))
    )
    (net (code "9") (name "/G_SW3") (class "Default")
      (node (ref "Q17") (pin "1") (pinfunction "G_1") (pintype "passive"))
      (node (ref "Q21") (pin "1") (pinfunction "G_1") (pintype "passive"))
      (node (ref "R17") (pin "1") (pinfunction "1_1") (pintype "passive"))
      (node (ref "R21") (pin "1") (pinfunction "1_1") (pintype "passive"))
    )
    (net (code "10") (name "/OPEN_0") (class "Default")
      (node (ref "Q12") (pin "2") (pinfunction "S_2") (pintype "passive"))
    )
    (net (code "11") (name "/OPEN_1") (class "Default")
      (node (ref "Q11") (pin "2") (pinfunction "S_2") (pintype "passive"))
    )
    (net (code "12") (name "/OPEN_2") (class "Default")
      (node (ref "Q10") (pin "2") (pinfunction "S_2") (pintype "passive"))
    )
    (net (code "13") (name "/OPEN_3") (class "Default")
      (node (ref "Q9") (pin "2") (pinfunction "S_2") (pintype "passive"))
    )
    (net (code "16") (name "/VDD_SW_0") (class "Default")
      (node (ref "D12") (pin "2") (pinfunction "C_2") (pintype "passive"))
      (node (ref "D16") (pin "2") (pinfunction "C_2") (pintype "passive"))
      (node (ref "D4") (pin "2") (pinfunction "C_2") (pintype "passive"))
      (node (ref "R16") (pin "2") (pinfunction "2_2") (pintype "passive"))
      (node (ref "R4") (pin "2") (pinfunction "2_2") (pintype "passive"))
      (node (ref "R8") (pin "2") (pinfunction "2_2") (pintype "passive"))
    )
    (net (code "17") (name "/VDD_SW_1") (class "Default")
      (node (ref "D11") (pin "2") (pinfunction "C_2") (pintype "passive"))
      (node (ref "D15") (pin "2") (pinfunction "C_2") (pintype "passive"))
      (node (ref "D3") (pin "2") (pinfunction "C_2") (pintype "passive"))
      (node (ref "R15") (pin "2") (pinfunction "2_2") (pintype "passive"))
      (node (ref "R3") (pin "2") (pinfunction "2_2") (pintype "passive"))
      (node (ref "R7") (pin "2") (pinfunction "2_2") (pintype "passive"))
    )
    (net (code "18") (name "/VDD_SW_2") (class "Default")
      (node (ref "D10") (pin "2") (pinfunction "C_2") (pintype "passive"))
      (node (ref "D14") (pin "2") (pinfunction "C_2") (pintype "passive"))
      (node (ref "D2") (pin "2") (pinfunction "C_2") (pintype "passive"))
      (node (ref "R14") (pin "2") (pinfunction "2_2") (pintype "passive"))
      (node (ref "R2") (pin "2") (pinfunction "2_2") (pintype "passive"))
      (node (ref "R6") (pin "2") (pinfunction "2_2") (pintype "passive"))
    )
    (net (code "19") (name "/VDD_SW_3") (class "Default")
      (node (ref "D1") (pin "2") (pinfunction "C_2") (pintype "passive"))
      (node (ref "D13") (pin "2") (pinfunction "C_2") (pintype "passive"))
      (node (ref "D9") (pin "2") (pinfunction "C_2") (pintype "passive"))
      (node (ref "R1") (pin "2") (pinfunction "2_2") (pintype "passive"))
      (node (ref "R13") (pin "2") (pinfunction "2_2") (pintype "passive"))
      (node (ref "R5") (pin "2") (pinfunction "2_2") (pintype "passive"))
    )
    (net (code "20") (name "/VLTCH_0") (class "Default")
      (node (ref "C25") (pin "2") (pinfunction "2_2") (pintype "passive"))
      (node (ref "D7") (pin "2") (pinfunction "C_2") (pintype "passive"))
      (node (ref "Q12") (pin "3") (pinfunction "D_3") (pintype "passive"))
      (node (ref "Q8") (pin "1") (pinfunction "G_1") (pintype "passive"))
      (node (ref "R12") (pin "2") (pinfunction "2_2") (pintype "passive"))
      (node (ref "R20") (pin "2") (pinfunction "2_2") (pintype "passive"))
    )
    (net (code "21") (name "/VLTCH_1") (class "Default")
      (node (ref "C24") (pin "2") (pinfunction "2_2") (pintype "passive"))
      (node (ref "D8") (pin "2") (pinfunction "C_2") (pintype "passive"))
      (node (ref "Q11") (pin "3") (pinfunction "D_3") (pintype "passive"))
      (node (ref "Q7") (pin "1") (pinfunction "G_1") (pintype "passive"))
      (node (ref "R11") (pin "2") (pinfunction "2_2") (pintype "passive"))
      (node (ref "R19") (pin "2") (pinfunction "2_2") (pintype "passive"))
    )
    (net (code "22") (name "/VLTCH_2") (class "Default")
      (node (ref "C23") (pin "2") (pinfunction "2_2") (pintype "passive"))
      (node (ref "D6") (pin "2") (pinfunction "C_2") (pintype "passive"))
      (node (ref "Q10") (pin "3") (pinfunction "D_3") (pintype "passive"))
      (node (ref "Q6") (pin "1") (pinfunction "G_1") (pintype "passive"))
      (node (ref "R10") (pin "2") (pinfunction "2_2") (pintype "passive"))
      (node (ref "R18") (pin "2") (pinfunction "2_2") (pintype "passive"))
    )
    (net (code "23") (name "/VLTCH_3") (class "Default")
      (node (ref "C22") (pin "2") (pinfunction "2_2") (pintype "passive"))
      (node (ref "D5") (pin "2") (pinfunction "C_2") (pintype "passive"))
      (node (ref "Q5") (pin "1") (pinfunction "G_1") (pintype "passive"))
      (node (ref "Q9") (pin "3") (pinfunction "D_3") (pintype "passive"))
      (node (ref "R17") (pin "2") (pinfunction "2_2") (pintype "passive"))
      (node (ref "R9") (pin "2") (pinfunction "2_2") (pintype "passive"))
    )
    (net (code "24") (name "GND") (class "Default")
      (node (ref "C1") (pin "2") (pinfunction "2_2") (pintype "passive"))
      (node (ref "C10") (pin "2") (pinfunction "2_2") (pintype "passive"))
      (node (ref "C11") (pin "2") (pinfunction "2_2") (pintype "passive"))
      (node (ref "C12") (pin "2") (pinfunction "2_2") (pintype "passive"))
      (node (ref "C13") (pin "2") (pinfunction "2_2") (pintype "passive"))
      (node (ref "C14") (pin "2") (pinfunction "2_2") (pintype "passive"))
      (node (ref "C15") (pin "2") (pinfunction "N_2") (pintype "passive"))
      (node (ref "C16") (pin "2") (pinfunction "N_2") (pintype "passive"))
      (node (ref "C17") (pin "2") (pinfunction "N_2") (pintype "passive"))
      (node (ref "C18") (pin "2") (pinfunction "N_2") (pintype "passive"))
      (node (ref "C19") (pin "2") (pinfunction "N_2") (pintype "passive"))
      (node (ref "C2") (pin "2") (pinfunction "2_2") (pintype "passive"))
      (node (ref "C22") (pin "1") (pinfunction "1_1") (pintype "passive"))
      (node (ref "C23") (pin "1") (pinfunction "1_1") (pintype "passive"))
      (node (ref "C24") (pin "1") (pinfunction "1_1") (pintype "passive"))
      (node (ref "C25") (pin "1") (pinfunction "1_1") (pintype "passive"))
      (node (ref "C3") (pin "2") (pinfunction "2_2") (pintype "passive"))
      (node (ref "C4") (pin "2") (pinfunction "2_2") (pintype "passive"))
      (node (ref "C5") (pin "2") (pinfunction "2_2") (pintype "passive"))
      (node (ref "C6") (pin "2") (pinfunction "2_2") (pintype "passive"))
      (node (ref "C7") (pin "2") (pinfunction "2_2") (pintype "passive"))
      (node (ref "C8") (pin "2") (pinfunction "2_2") (pintype "passive"))
      (node (ref "C9") (pin "2") (pinfunction "2_2") (pintype "passive"))
      (node (ref "Q13") (pin "2") (pinfunction "S_2") (pintype "passive"))
      (node (ref "Q14") (pin "2") (pinfunction "S_2") (pintype "passive"))
      (node (ref "Q15") (pin "2") (pinfunction "S_2") (pintype "passive"))
      (node (ref "Q16") (pin "2") (pinfunction "S_2") (pintype "passive"))
      (node (ref "Q5") (pin "2") (pinfunction "S_2") (pintype "passive"))
      (node (ref "Q6") (pin "2") (pinfunction "S_2") (pintype "passive"))
      (node (ref "Q7") (pin "2") (pinfunction "S_2") (pintype "passive"))
      (node (ref "Q8") (pin "2") (pinfunction "S_2") (pintype "passive"))
    )
    (net (code "25") (name "Net-(D5-A)") (class "Default")
      (node (ref "D5") (pin "1") (pinfunction "A_1") (pintype "passive"))
      (node (ref "Q1") (pin "3") (pinfunction "D_3") (pintype "passive"))
    )
    (net (code "26") (name "Net-(D6-A)") (class "Default")
      (node (ref "D6") (pin "1") (pinfunction "A_1") (pintype "passive"))
      (node (ref "Q2") (pin "3") (pinfunction "D_3") (pintype "passive"))
    )
    (net (code "27") (name "Net-(D7-A)") (class "Default")
      (node (ref "D7") (pin "1") (pinfunction "A_1") (pintype "passive"))
      (node (ref "Q4") (pin "3") (pinfunction "D_3") (pintype "passive"))
    )
    (net (code "28") (name "Net-(D8-A)") (class "Default")
      (node (ref "D8") (pin "1") (pinfunction "A_1") (pintype "passive"))
      (node (ref "Q3") (pin "3") (pinfunction "D_3") (pintype "passive"))
    )
    (net (code "29") (name "Net-(D10-A)") (class "Default")
      (node (ref "D10") (pin "1") (pinfunction "A_1") (pintype "passive"))
      (node (ref "D17") (pin "2") (pinfunction "C_2") (pintype "passive"))
      (node (ref "D9") (pin "1") (pinfunction "A_1") (pintype "passive"))
      (node (ref "Q17") (pin "2") (pinfunction "S_2") (pintype "passive"))
      (node (ref "R25") (pin "1") (pinfunction "1_1") (pintype "passive"))
    )
    (net (code "30") (name "Net-(D11-A)") (class "Default")
      (node (ref "D11") (pin "1") (pinfunction "A_1") (pintype "passive"))
      (node (ref "D18") (pin "2") (pinfunction "C_2") (pintype "passive"))
      (node (ref "Q18") (pin "2") (pinfunction "S_2") (pintype "passive"))
      (node (ref "R25") (pin "2") (pinfunction "2_2") (pintype "passive"))
      (node (ref "R26") (pin "1") (pinfunction "1_1") (pintype "passive"))
    )
    (net (code "31") (name "Net-(D12-A)") (class "Default")
      (node (ref "D12") (pin "1") (pinfunction "A_1") (pintype "passive"))
      (node (ref "D19") (pin "2") (pinfunction "C_2") (pintype "passive"))
      (node (ref "Q19") (pin "2") (pinfunction "S_2") (pintype "passive"))
      (node (ref "R26") (pin "2") (pinfunction "2_2") (pintype "passive"))
      (node (ref "R27") (pin "1") (pinfunction "1_1") (pintype "passive"))
    )
    (net (code "32") (name "Net-(D17-A)") (class "Default")
      (node (ref "D17") (pin "1") (pinfunction "A_1") (pintype "passive"))
      (node (ref "D21") (pin "1") (pinfunction "A_1") (pintype "passive"))
      (node (ref "Q17") (pin "3") (pinfunction "D_3") (pintype "passive"))
      (node (ref "Q21") (pin "3") (pinfunction "D_3") (pintype "passive"))
    )
    (net (code "33") (name "Net-(D18-A)") (class "Default")
      (node (ref "D18") (pin "1") (pinfunction "A_1") (pintype "passive"))
      (node (ref "D22") (pin "1") (pinfunction "A_1") (pintype "passive"))
      (node (ref "Q18") (pin "3") (pinfunction "D_3") (pintype "passive"))
      (node (ref "Q22") (pin "3") (pinfunction "D_3") (pintype "passive"))
    )
    (net (code "34") (name "Net-(D19-A)") (class "Default")
      (node (ref "D19") (pin "1") (pinfunction "A_1") (pintype "passive"))
      (node (ref "D23") (pin "1") (pinfunction "A_1") (pintype "passive"))
      (node (ref "Q19") (pin "3") (pinfunction "D_3") (pintype "passive"))
      (node (ref "Q23") (pin "3") (pinfunction "D_3") (pintype "passive"))
    )
    (net (code "35") (name "Net-(D20-A)") (class "Default")
      (node (ref "D20") (pin "1") (pinfunction "A_1") (pintype "passive"))
      (node (ref "D24") (pin "1") (pinfunction "A_1") (pintype "passive"))
      (node (ref "Q20") (pin "3") (pinfunction "D_3") (pintype "passive"))
      (node (ref "Q24") (pin "3") (pinfunction "D_3") (pintype "passive"))
    )
    (net (code "36") (name "Net-(D20-C)") (class "Default")
      (node (ref "D20") (pin "2") (pinfunction "C_2") (pintype "passive"))
      (node (ref "Q20") (pin "2") (pinfunction "S_2") (pintype "passive"))
      (node (ref "R27") (pin "2") (pinfunction "2_2") (pintype "passive"))
      (node (ref "R28") (pin "1") (pinfunction "1_1") (pintype "passive"))
    )
    (net (code "37") (name "Net-(Q1-G)") (class "Default")
      (node (ref "Q1") (pin "1") (pinfunction "G_1") (pintype "passive"))
      (node (ref "Q5") (pin "3") (pinfunction "D_3") (pintype "passive"))
      (node (ref "R5") (pin "1") (pinfunction "1_1") (pintype "passive"))
    )
    (net (code "38") (name "Net-(Q1-S)") (class "Default")
      (node (ref "Q1") (pin "2") (pinfunction "S_2") (pintype "passive"))
      (node (ref "R1") (pin "1") (pinfunction "1_1") (pintype "passive"))
    )
    (net (code "39") (name "Net-(Q2-G)") (class "Default")
      (node (ref "Q2") (pin "1") (pinfunction "G_1") (pintype "passive"))
      (node (ref "Q6") (pin "3") (pinfunction "D_3") (pintype "passive"))
      (node (ref "R6") (pin "1") (pinfunction "1_1") (pintype "passive"))
    )
    (net (code "40") (name "Net-(Q2-S)") (class "Default")
      (node (ref "Q2") (pin "2") (pinfunction "S_2") (pintype "passive"))
      (node (ref "R2") (pin "1") (pinfunction "1_1") (pintype "passive"))
    )
    (net (code "41") (name "Net-(Q3-G)") (class "Default")
      (node (ref "Q3") (pin "1") (pinfunction "G_1") (pintype "passive"))
      (node (ref "Q7") (pin "3") (pinfunction "D_3") (pintype "passive"))
      (node (ref "R7") (pin "1") (pinfunction "1_1") (pintype "passive"))
    )
    (net (code "42") (name "Net-(Q3-S)") (class "Default")
      (node (ref "Q3") (pin "2") (pinfunction "S_2") (pintype "passive"))
      (node (ref "R3") (pin "1") (pinfunction "1_1") (pintype "passive"))
    )
    (net (code "43") (name "Net-(Q4-G)") (class "Default")
      (node (ref "Q4") (pin "1") (pinfunction "G_1") (pintype "passive"))
      (node (ref "Q8") (pin "3") (pinfunction "D_3") (pintype "passive"))
      (node (ref "R8") (pin "1") (pinfunction "1_1") (pintype "passive"))
    )
    (net (code "44") (name "Net-(Q4-S)") (class "Default")
      (node (ref "Q4") (pin "2") (pinfunction "S_2") (pintype "passive"))
      (node (ref "R4") (pin "1") (pinfunction "1_1") (pintype "passive"))
    )
    (net (code "45") (name "Net-(Q13-D)") (class "Default")
      (node (ref "Q13") (pin "3") (pinfunction "D_3") (pintype "passive"))
      (node (ref "R13") (pin "1") (pinfunction "1_1") (pintype "passive"))
      (node (ref "R21") (pin "2") (pinfunction "2_2") (pintype "passive"))
    )
    (net (code "46") (name "Net-(Q13-G)") (class "Default")
      (node (ref "Q13") (pin "1") (pinfunction "G_1") (pintype "passive"))
      (node (ref "R9") (pin "1") (pinfunction "1_1") (pintype "passive"))
    )
    (net (code "47") (name "Net-(Q14-D)") (class "Default")
      (node (ref "Q14") (pin "3") (pinfunction "D_3") (pintype "passive"))
      (node (ref "R14") (pin "1") (pinfunction "1_1") (pintype "passive"))
      (node (ref "R22") (pin "2") (pinfunction "2_2") (pintype "passive"))
    )
    (net (code "48") (name "Net-(Q14-G)") (class "Default")
      (node (ref "Q14") (pin "1") (pinfunction "G_1") (pintype "passive"))
      (node (ref "R10") (pin "1") (pinfunction "1_1") (pintype "passive"))
    )
    (net (code "49") (name "Net-(Q15-D)") (class "Default")
      (node (ref "Q15") (pin "3") (pinfunction "D_3") (pintype "passive"))
      (node (ref "R15") (pin "1") (pinfunction "1_1") (pintype "passive"))
      (node (ref "R23") (pin "2") (pinfunction "2_2") (pintype "passive"))
    )
    (net (code "50") (name "Net-(Q15-G)") (class "Default")
      (node (ref "Q15") (pin "1") (pinfunction "G_1") (pintype "passive"))
      (node (ref "R11") (pin "1") (pinfunction "1_1") (pintype "passive"))
    )
    (net (code "51") (name "Net-(Q16-D)") (class "Default")
      (node (ref "Q16") (pin "3") (pinfunction "D_3") (pintype "passive"))
      (node (ref "R16") (pin "1") (pinfunction "1_1") (pintype "passive"))
      (node (ref "R24") (pin "2") (pinfunction "2_2") (pintype "passive"))
    )
    (net (code "52") (name "Net-(Q16-G)") (class "Default")
      (node (ref "Q16") (pin "1") (pinfunction "G_1") (pintype "passive"))
      (node (ref "R12") (pin "1") (pinfunction "1_1") (pintype "passive"))
    )
    (net (code "53") (name "VCAP") (class "Default")
      (node (ref "C1") (pin "1") (pinfunction "1_1") (pintype "passive"))
      (node (ref "C2") (pin "1") (pinfunction "1_1") (pintype "passive"))
      (node (ref "R28") (pin "2") (pinfunction "2_2") (pintype "passive"))
      (node (ref "R32") (pin "2") (pinfunction "2_2") (pintype "passive"))
    )
    (net (code "54") (name "VDD_LOAD") (class "Default")
      (node (ref "D1") (pin "1") (pinfunction "A_1") (pintype "passive"))
      (node (ref "D2") (pin "1") (pinfunction "A_1") (pintype "passive"))
      (node (ref "D3") (pin "1") (pinfunction "A_1") (pintype "passive"))
      (node (ref "D4") (pin "1") (pinfunction "A_1") (pintype "passive"))
      (node (ref "Q10") (pin "1") (pinfunction "G_1") (pintype "passive"))
      (node (ref "Q11") (pin "1") (pinfunction "G_1") (pintype "passive"))
      (node (ref "Q12") (pin "1") (pinfunction "G_1") (pintype "passive"))
      (node (ref "Q9") (pin "1") (pinfunction "G_1") (pintype "passive"))
    )
  )
)
